# XTXBoard2.net
KiCad netlist of a schematic drawn in Altium Designer
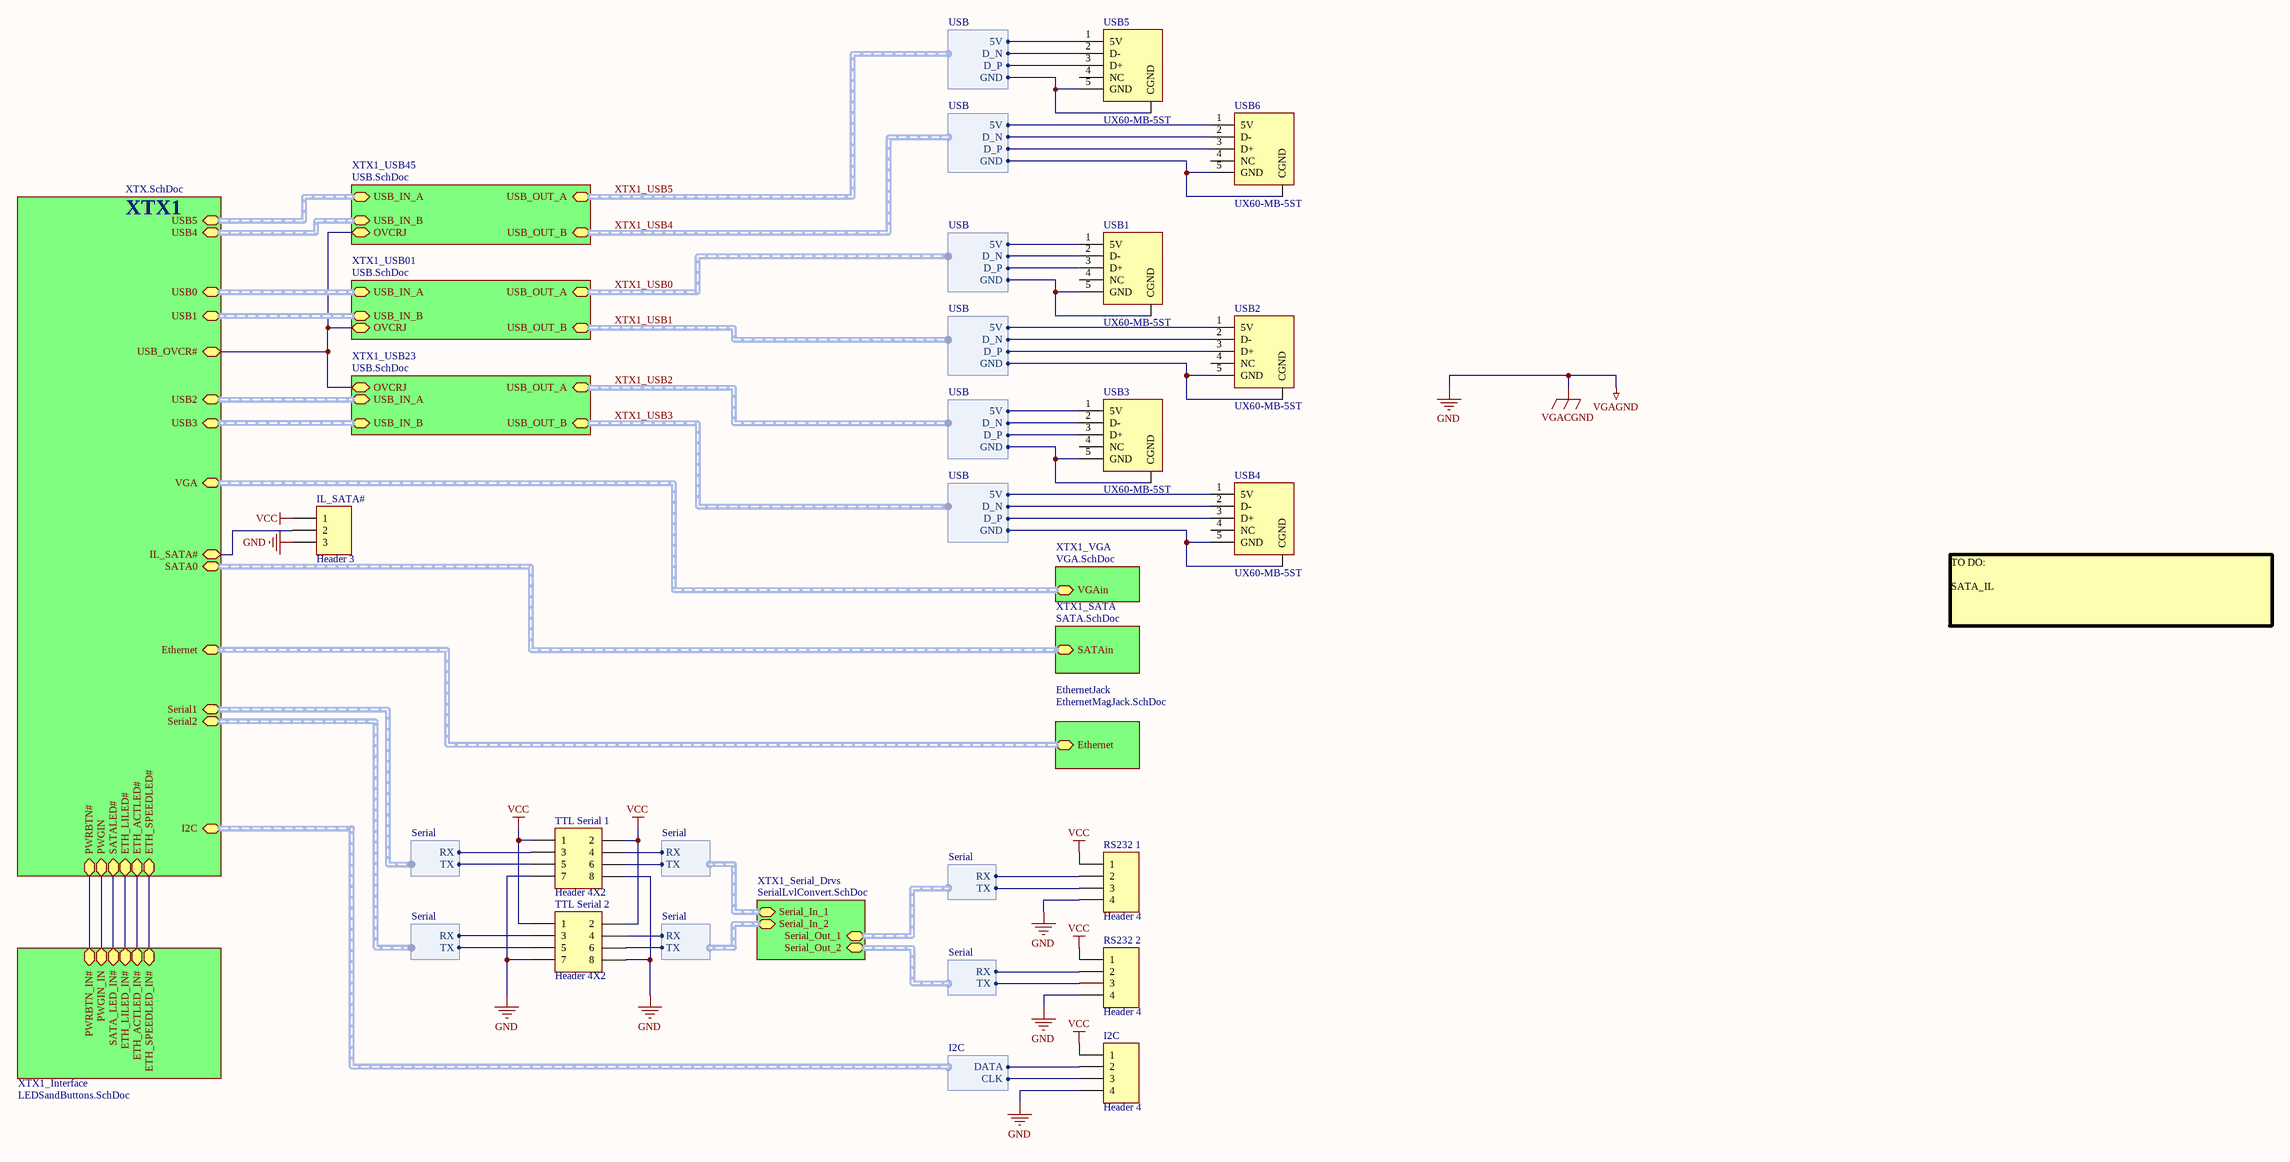
[diagram p0: XTXBoard2.SchDoc]

(export (version "E")
  (design (tool "Eeschema 10.0.6"))
  (components
    (comp (ref "I2C")
      (value "Header 4")
      (footprint "HDR1X4")
      (description "Header, 4-Pin")
      (fields (field (name "PUBLISHER") "Altium Limited"))
      (libsource (lib "Miscellaneous Connectors") (part "Header 4"))
    )
    (comp (ref "IL_SATA#")
      (value "Header 3")
      (footprint "HDR1X3")
      (description "Header, 3-Pin")
      (fields (field (name "PUBLISHER") "Altium Limited"))
      (libsource (lib "Miscellaneous Connectors") (part "Header 3"))
    )
    (comp (ref "RS232 1")
      (value "Header 4")
      (footprint "HDR1X4")
      (description "Header, 4-Pin")
      (fields (field (name "PUBLISHER") "Altium Limited"))
      (libsource (lib "Miscellaneous Connectors") (part "Header 4"))
    )
    (comp (ref "RS232 2")
      (value "Header 4")
      (footprint "HDR1X4")
      (description "Header, 4-Pin")
      (fields (field (name "PUBLISHER") "Altium Limited"))
      (libsource (lib "Miscellaneous Connectors") (part "Header 4"))
    )
    (comp (ref "TTL Serial 1")
      (value "Header 4X2")
      (footprint "HDR2X4")
      (description "Header, 4-Pin, Dual row")
      (fields (field (name "PUBLISHER") "Altium Limited"))
      (libsource (lib "Miscellaneous Connectors") (part "Header 4X2"))
    )
    (comp (ref "TTL Serial 2")
      (value "Header 4X2")
      (footprint "HDR2X4")
      (description "Header, 4-Pin, Dual row")
      (fields (field (name "PUBLISHER") "Altium Limited"))
      (libsource (lib "Miscellaneous Connectors") (part "Header 4X2"))
    )
    (comp (ref "USB1")
      (value "UX60-MB-5ST")
      (footprint "Hirose:UX60-MB-5ST")
      (description "miniUSB Type B SMT Connector")
      (libsource (lib "Hirose") (part "UX60-MB-5ST"))
    )
    (comp (ref "USB2")
      (value "UX60-MB-5ST")
      (footprint "Hirose:UX60-MB-5ST")
      (description "miniUSB Type B SMT Connector")
      (libsource (lib "Hirose") (part "UX60-MB-5ST"))
    )
    (comp (ref "USB3")
      (value "UX60-MB-5ST")
      (footprint "Hirose:UX60-MB-5ST")
      (description "miniUSB Type B SMT Connector")
      (libsource (lib "Hirose") (part "UX60-MB-5ST"))
    )
    (comp (ref "USB4")
      (value "UX60-MB-5ST")
      (footprint "Hirose:UX60-MB-5ST")
      (description "miniUSB Type B SMT Connector")
      (libsource (lib "Hirose") (part "UX60-MB-5ST"))
    )
    (comp (ref "USB5")
      (value "UX60-MB-5ST")
      (footprint "Hirose:UX60-MB-5ST")
      (description "miniUSB Type B SMT Connector")
      (libsource (lib "Hirose") (part "UX60-MB-5ST"))
    )
    (comp (ref "USB6")
      (value "UX60-MB-5ST")
      (footprint "Hirose:UX60-MB-5ST")
      (description "miniUSB Type B SMT Connector")
      (libsource (lib "Hirose") (part "UX60-MB-5ST"))
    )
  )
  (nets
    (net (code "9") (name "/CLK") (class "Default")
      (node (ref "I2C") (pin "3") (pinfunction "3_3") (pintype "passive"))
    )
    (net (code "10") (name "/DATA") (class "Default")
      (node (ref "I2C") (pin "2") (pinfunction "2_2") (pintype "passive"))
    )
    (net (code "15") (name "/IL_SATA#") (class "Default")
      (node (ref "IL_SATA#") (pin "2") (pinfunction "2_2") (pintype "passive"))
    )
    (net (code "36") (name "GND") (class "Default")
      (node (ref "I2C") (pin "4") (pinfunction "4_4") (pintype "passive"))
      (node (ref "IL_SATA#") (pin "3") (pinfunction "3_3") (pintype "passive"))
      (node (ref "RS232 1") (pin "4") (pinfunction "4_4") (pintype "passive"))
      (node (ref "RS232 2") (pin "4") (pinfunction "4_4") (pintype "passive"))
      (node (ref "TTL Serial 1") (pin "7") (pinfunction "7_7") (pintype "passive"))
      (node (ref "TTL Serial 1") (pin "8") (pinfunction "8_8") (pintype "passive"))
      (node (ref "TTL Serial 2") (pin "7") (pinfunction "7_7") (pintype "passive"))
      (node (ref "TTL Serial 2") (pin "8") (pinfunction "8_8") (pintype "passive"))
    )
    (net (code "37") (name "Net-(USB1-GND)") (class "Default")
      (node (ref "USB1") (pin "5") (pinfunction "GND_5") (pintype "passive"))
      (node (ref "USB1") (pin "CGND") (pinfunction "CGND_CGND") (pintype "passive"))
    )
    (net (code "38") (name "Net-(USB2-GND)") (class "Default")
      (node (ref "USB2") (pin "5") (pinfunction "GND_5") (pintype "passive"))
      (node (ref "USB2") (pin "CGND") (pinfunction "CGND_CGND") (pintype "passive"))
    )
    (net (code "39") (name "Net-(USB3-GND)") (class "Default")
      (node (ref "USB3") (pin "5") (pinfunction "GND_5") (pintype "passive"))
      (node (ref "USB3") (pin "CGND") (pinfunction "CGND_CGND") (pintype "passive"))
    )
    (net (code "40") (name "Net-(USB4-GND)") (class "Default")
      (node (ref "USB4") (pin "5") (pinfunction "GND_5") (pintype "passive"))
      (node (ref "USB4") (pin "CGND") (pinfunction "CGND_CGND") (pintype "passive"))
    )
    (net (code "41") (name "Net-(USB5-GND)") (class "Default")
      (node (ref "USB5") (pin "5") (pinfunction "GND_5") (pintype "passive"))
      (node (ref "USB5") (pin "CGND") (pinfunction "CGND_CGND") (pintype "passive"))
    )
    (net (code "42") (name "Net-(USB6-GND)") (class "Default")
      (node (ref "USB6") (pin "5") (pinfunction "GND_5") (pintype "passive"))
      (node (ref "USB6") (pin "CGND") (pinfunction "CGND_CGND") (pintype "passive"))
    )
    (net (code "43") (name "VCC") (class "Default")
      (node (ref "I2C") (pin "1") (pinfunction "1_1") (pintype "passive"))
      (node (ref "IL_SATA#") (pin "1") (pinfunction "1_1") (pintype "passive"))
      (node (ref "RS232 1") (pin "1") (pinfunction "1_1") (pintype "passive"))
      (node (ref "RS232 2") (pin "1") (pinfunction "1_1") (pintype "passive"))
      (node (ref "TTL Serial 1") (pin "1") (pinfunction "1_1") (pintype "passive"))
      (node (ref "TTL Serial 1") (pin "2") (pinfunction "2_2") (pintype "passive"))
      (node (ref "TTL Serial 2") (pin "1") (pinfunction "1_1") (pintype "passive"))
      (node (ref "TTL Serial 2") (pin "2") (pinfunction "2_2") (pintype "passive"))
    )
    (net (code "44") (name "unconnected-(RS232 1-Pad2)") (class "Default")
      (node (ref "RS232 1") (pin "2") (pinfunction "2_2") (pintype "passive"))
    )
    (net (code "45") (name "unconnected-(RS232 1-Pad3)") (class "Default")
      (node (ref "RS232 1") (pin "3") (pinfunction "3_3") (pintype "passive"))
    )
    (net (code "46") (name "unconnected-(RS232 2-Pad2)") (class "Default")
      (node (ref "RS232 2") (pin "2") (pinfunction "2_2") (pintype "passive"))
    )
    (net (code "47") (name "unconnected-(RS232 2-Pad3)") (class "Default")
      (node (ref "RS232 2") (pin "3") (pinfunction "3_3") (pintype "passive"))
    )
    (net (code "48") (name "unconnected-(TTL Serial 1-Pad3)") (class "Default")
      (node (ref "TTL Serial 1") (pin "3") (pinfunction "3_3") (pintype "passive"))
    )
    (net (code "49") (name "unconnected-(TTL Serial 1-Pad4)") (class "Default")
      (node (ref "TTL Serial 1") (pin "4") (pinfunction "4_4") (pintype "passive"))
    )
    (net (code "50") (name "unconnected-(TTL Serial 1-Pad5)") (class "Default")
      (node (ref "TTL Serial 1") (pin "5") (pinfunction "5_5") (pintype "passive"))
    )
    (net (code "51") (name "unconnected-(TTL Serial 1-Pad6)") (class "Default")
      (node (ref "TTL Serial 1") (pin "6") (pinfunction "6_6") (pintype "passive"))
    )
    (net (code "52") (name "unconnected-(TTL Serial 2-Pad3)") (class "Default")
      (node (ref "TTL Serial 2") (pin "3") (pinfunction "3_3") (pintype "passive"))
    )
    (net (code "53") (name "unconnected-(TTL Serial 2-Pad4)") (class "Default")
      (node (ref "TTL Serial 2") (pin "4") (pinfunction "4_4") (pintype "passive"))
    )
    (net (code "54") (name "unconnected-(TTL Serial 2-Pad5)") (class "Default")
      (node (ref "TTL Serial 2") (pin "5") (pinfunction "5_5") (pintype "passive"))
    )
    (net (code "55") (name "unconnected-(TTL Serial 2-Pad6)") (class "Default")
      (node (ref "TTL Serial 2") (pin "6") (pinfunction "6_6") (pintype "passive"))
    )
    (net (code "56") (name "unconnected-(USB1-5V-Pad1)") (class "Default")
      (node (ref "USB1") (pin "1") (pinfunction "5V_1") (pintype "passive"))
    )
    (net (code "57") (name "unconnected-(USB1-D+-Pad3)") (class "Default")
      (node (ref "USB1") (pin "3") (pinfunction "D+_3") (pintype "passive"))
    )
    (net (code "58") (name "unconnected-(USB1-D--Pad2)") (class "Default")
      (node (ref "USB1") (pin "2") (pinfunction "D-_2") (pintype "passive"))
    )
    (net (code "59") (name "unconnected-(USB1-NC-Pad4)") (class "Default")
      (node (ref "USB1") (pin "4") (pinfunction "NC_4") (pintype "passive"))
    )
    (net (code "60") (name "unconnected-(USB2-5V-Pad1)") (class "Default")
      (node (ref "USB2") (pin "1") (pinfunction "5V_1") (pintype "passive"))
    )
    (net (code "61") (name "unconnected-(USB2-D+-Pad3)") (class "Default")
      (node (ref "USB2") (pin "3") (pinfunction "D+_3") (pintype "passive"))
    )
    (net (code "62") (name "unconnected-(USB2-D--Pad2)") (class "Default")
      (node (ref "USB2") (pin "2") (pinfunction "D-_2") (pintype "passive"))
    )
    (net (code "63") (name "unconnected-(USB2-NC-Pad4)") (class "Default")
      (node (ref "USB2") (pin "4") (pinfunction "NC_4") (pintype "passive"))
    )
    (net (code "64") (name "unconnected-(USB3-5V-Pad1)") (class "Default")
      (node (ref "USB3") (pin "1") (pinfunction "5V_1") (pintype "passive"))
    )
    (net (code "65") (name "unconnected-(USB3-D+-Pad3)") (class "Default")
      (node (ref "USB3") (pin "3") (pinfunction "D+_3") (pintype "passive"))
    )
    (net (code "66") (name "unconnected-(USB3-D--Pad2)") (class "Default")
      (node (ref "USB3") (pin "2") (pinfunction "D-_2") (pintype "passive"))
    )
    (net (code "67") (name "unconnected-(USB3-NC-Pad4)") (class "Default")
      (node (ref "USB3") (pin "4") (pinfunction "NC_4") (pintype "passive"))
    )
    (net (code "68") (name "unconnected-(USB4-5V-Pad1)") (class "Default")
      (node (ref "USB4") (pin "1") (pinfunction "5V_1") (pintype "passive"))
    )
    (net (code "69") (name "unconnected-(USB4-D+-Pad3)") (class "Default")
      (node (ref "USB4") (pin "3") (pinfunction "D+_3") (pintype "passive"))
    )
    (net (code "70") (name "unconnected-(USB4-D--Pad2)") (class "Default")
      (node (ref "USB4") (pin "2") (pinfunction "D-_2") (pintype "passive"))
    )
    (net (code "71") (name "unconnected-(USB4-NC-Pad4)") (class "Default")
      (node (ref "USB4") (pin "4") (pinfunction "NC_4") (pintype "passive"))
    )
    (net (code "72") (name "unconnected-(USB5-5V-Pad1)") (class "Default")
      (node (ref "USB5") (pin "1") (pinfunction "5V_1") (pintype "passive"))
    )
    (net (code "73") (name "unconnected-(USB5-D+-Pad3)") (class "Default")
      (node (ref "USB5") (pin "3") (pinfunction "D+_3") (pintype "passive"))
    )
    (net (code "74") (name "unconnected-(USB5-D--Pad2)") (class "Default")
      (node (ref "USB5") (pin "2") (pinfunction "D-_2") (pintype "passive"))
    )
    (net (code "75") (name "unconnected-(USB5-NC-Pad4)") (class "Default")
      (node (ref "USB5") (pin "4") (pinfunction "NC_4") (pintype "passive"))
    )
    (net (code "76") (name "unconnected-(USB6-5V-Pad1)") (class "Default")
      (node (ref "USB6") (pin "1") (pinfunction "5V_1") (pintype "passive"))
    )
    (net (code "77") (name "unconnected-(USB6-D+-Pad3)") (class "Default")
      (node (ref "USB6") (pin "3") (pinfunction "D+_3") (pintype "passive"))
    )
    (net (code "78") (name "unconnected-(USB6-D--Pad2)") (class "Default")
      (node (ref "USB6") (pin "2") (pinfunction "D-_2") (pintype "passive"))
    )
    (net (code "79") (name "unconnected-(USB6-NC-Pad4)") (class "Default")
      (node (ref "USB6") (pin "4") (pinfunction "NC_4") (pintype "passive"))
    )
  )
)
